# CH564L-R0-1v0.net
KiCad netlist of a schematic drawn in Altium Designer
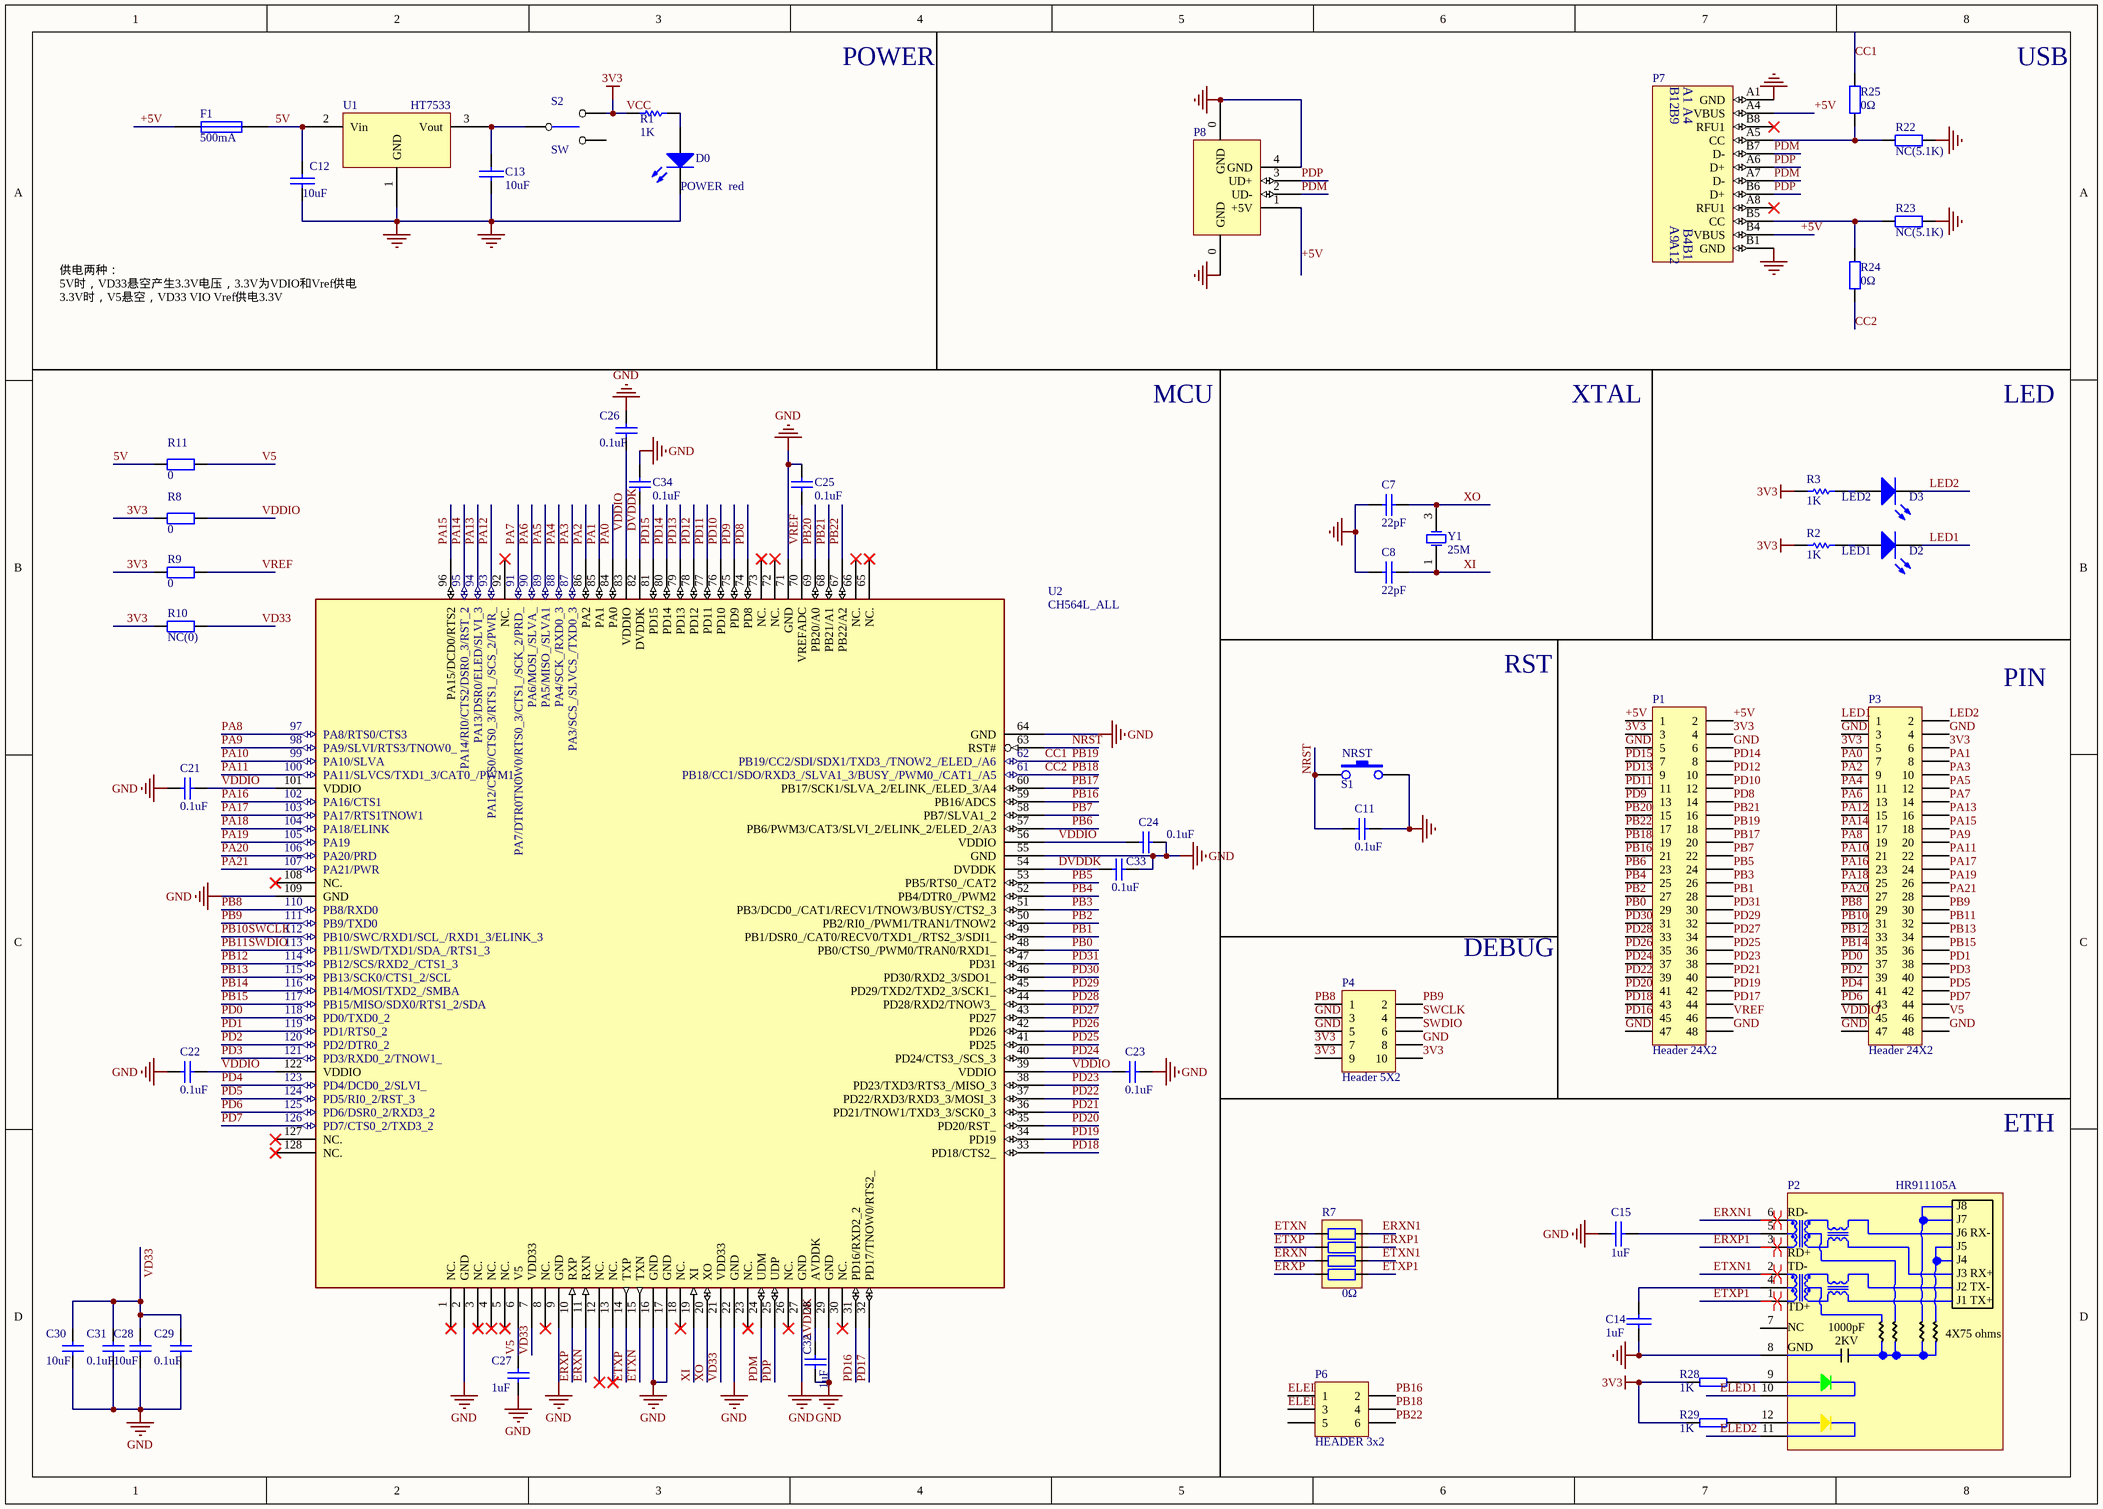
[diagram p0: CH564L-R0-1v0.SchDoc]

(export (version "E")
  (design (tool "Eeschema 10.0.6"))
  (components
    (comp (ref "C7")
      (value "22pF")
      (footprint "0402_C")
      (description "Capacitor")
      (fields (field (name "PUBLISHER") "Altium Limited"))
      (libsource (lib "*") (part "Cap"))
    )
    (comp (ref "C8")
      (value "22pF")
      (footprint "0402_C")
      (description "Capacitor")
      (fields (field (name "PUBLISHER") "Altium Limited"))
      (libsource (lib "*") (part "Cap"))
    )
    (comp (ref "C11")
      (value "0.1uF")
      (footprint "0402_C")
      (description "Capacitor")
      (fields (field (name "PUBLISHER") "Altium Limited"))
      (libsource (lib "*") (part "Cap"))
    )
    (comp (ref "C12")
      (value "10uF")
      (footprint "0603_C")
      (description "Capacitor")
      (libsource (lib "*") (part "CAP"))
    )
    (comp (ref "C13")
      (value "10uF")
      (footprint "0603_C")
      (description "Capacitor")
      (libsource (lib "*") (part "CAP"))
    )
    (comp (ref "C14")
      (value "1uF")
      (footprint "0402_C")
      (description "Capacitor")
      (libsource (lib "*") (part "CAP"))
    )
    (comp (ref "C15")
      (value "1uF")
      (footprint "0402_C")
      (description "Capacitor")
      (libsource (lib "*") (part "CAP"))
    )
    (comp (ref "C21")
      (value "0.1uF")
      (footprint "0402_C")
      (description "Capacitor")
      (fields (field (name "PUBLISHER") "Altium Limited"))
      (libsource (lib "MYLIB") (part "C-RAD-0603"))
    )
    (comp (ref "C22")
      (value "0.1uF")
      (footprint "0402_C")
      (description "Capacitor")
      (fields (field (name "PUBLISHER") "Altium Limited"))
      (libsource (lib "MYLIB") (part "C-RAD-0603"))
    )
    (comp (ref "C23")
      (value "0.1uF")
      (footprint "0402_C")
      (description "Capacitor")
      (fields (field (name "PUBLISHER") "Altium Limited"))
      (libsource (lib "MYLIB") (part "C-RAD-0603"))
    )
    (comp (ref "C24")
      (value "0.1uF")
      (footprint "0402_C")
      (description "Capacitor")
      (fields (field (name "PUBLISHER") "Altium Limited"))
      (libsource (lib "MYLIB") (part "C-RAD-0603"))
    )
    (comp (ref "C25")
      (value "0.1uF")
      (footprint "0402_C")
      (description "Capacitor")
      (fields (field (name "PUBLISHER") "Altium Limited"))
      (libsource (lib "MYLIB") (part "C-RAD-0603"))
    )
    (comp (ref "C26")
      (value "0.1uF")
      (footprint "0402_C")
      (description "Capacitor")
      (fields (field (name "PUBLISHER") "Altium Limited"))
      (libsource (lib "MYLIB") (part "C-RAD-0603"))
    )
    (comp (ref "C27")
      (value "1uF")
      (footprint "0402_C")
      (description "Capacitor")
      (fields (field (name "PUBLISHER") "Altium Limited"))
      (libsource (lib "MYLIB") (part "C-RAD-0603"))
    )
    (comp (ref "C28")
      (value "10uF")
      (footprint "0603_C")
      (description "Capacitor")
      (fields (field (name "PUBLISHER") "Altium Limited"))
      (libsource (lib "MYLIB") (part "C-RAD-0603"))
    )
    (comp (ref "C29")
      (value "0.1uF")
      (footprint "0402_C")
      (description "Capacitor")
      (fields (field (name "PUBLISHER") "Altium Limited"))
      (libsource (lib "MYLIB") (part "C-RAD-0603"))
    )
    (comp (ref "C30")
      (value "10uF")
      (footprint "0603_C")
      (description "Capacitor")
      (fields (field (name "PUBLISHER") "Altium Limited"))
      (libsource (lib "MYLIB") (part "C-RAD-0603"))
    )
    (comp (ref "C31")
      (value "0.1uF")
      (footprint "0402_C")
      (description "Capacitor")
      (fields (field (name "PUBLISHER") "Altium Limited"))
      (libsource (lib "MYLIB") (part "C-RAD-0603"))
    )
    (comp (ref "C32")
      (value "1uF")
      (footprint "0402_C")
      (description "Capacitor")
      (fields (field (name "PUBLISHER") "Altium Limited"))
      (libsource (lib "MYLIB") (part "C-RAD-0603"))
    )
    (comp (ref "C33")
      (value "0.1uF")
      (footprint "0402_C")
      (description "Capacitor")
      (fields (field (name "PUBLISHER") "Altium Limited"))
      (libsource (lib "MYLIB") (part "C-RAD-0603"))
    )
    (comp (ref "C34")
      (value "0.1uF")
      (footprint "0402_C")
      (description "Capacitor")
      (fields (field (name "PUBLISHER") "Altium Limited"))
      (libsource (lib "MYLIB") (part "C-RAD-0603"))
    )
    (comp (ref "D0")
      (value "POWER  red")
      (footprint "0603+")
      (description "Typical INFRARED GaAs LED")
      (fields (field (name "PUBLISHER") "Altium Limited"))
      (libsource (lib "*") (part "LED0"))
    )
    (comp (ref "D2")
      (value "LED1")
      (footprint "0603+")
      (description "Typical INFRARED GaAs LED")
      (fields (field (name "PUBLISHER") "Altium Limited"))
      (libsource (lib "*") (part "LED0"))
    )
    (comp (ref "D3")
      (value "LED2")
      (footprint "0603+")
      (description "Typical INFRARED GaAs LED")
      (fields (field (name "PUBLISHER") "Altium Limited"))
      (libsource (lib "*") (part "LED0"))
    )
    (comp (ref "F1")
      (value "500mA")
      (footprint "0603")
      (description "Fuse")
      (libsource (lib "*") (part "FUSE1"))
    )
    (comp (ref "P1")
      (value "Header 24X2")
      (footprint "IDC48-2.54mm")
      (description "Header, 24-Pin, Dual row")
      (fields (field (name "PUBLISHER") "Altium Limited"))
      (libsource (lib "Miscellaneous Connectors") (part "Header 24X2"))
    )
    (comp (ref "P2") (value "HR911105A") (footprint "HR911105A") (libsource (lib "*") (part "HR911105A")))
    (comp (ref "P3")
      (value "Header 24X2")
      (footprint "IDC48-2.54mm")
      (description "Header, 24-Pin, Dual row")
      (fields (field (name "PUBLISHER") "Altium Limited"))
      (libsource (lib "Miscellaneous Connectors") (part "Header 24X2"))
    )
    (comp (ref "P4")
      (value "Header 5X2")
      (footprint "IDC10-2.54mm")
      (description "Header, 5-Pin, Dual row")
      (fields (field (name "PUBLISHER") "Altium Limited"))
      (libsource (lib "Miscellaneous Connectors") (part "Header 5X2"))
    )
    (comp (ref "P6")
      (value "HEADER 3x2")
      (footprint "MYPCB:IDC6-2.54mm")
      (description "Header, 3-Pin, Dual row")
      (libsource (lib "wch_sch_others") (part "HEADER 3x2"))
    )
    (comp (ref "P7")
      (value "TYPE-C")
      (footprint "TYPE-C-Receptacle-2.0")
      (libsource (lib "*") (part "TYPE-C1"))
    )
    (comp (ref "P8")
      (value "USB_A")
      (footprint "USBAF")
      (description "USB Port")
      (libsource (lib "*") (part "USB"))
    )
    (comp (ref "R1")
      (value "1K")
      (footprint "0402")
      (description "Semiconductor Resistor")
      (libsource (lib "*") (part "Res Semi"))
    )
    (comp (ref "R2")
      (value "1K")
      (footprint "0402")
      (description "Semiconductor Resistor")
      (fields (field (name "PUBLISHER") "Altium Limited"))
      (libsource (lib "*") (part "Res Semi"))
    )
    (comp (ref "R3")
      (value "1K")
      (footprint "0402")
      (description "Semiconductor Resistor")
      (fields (field (name "PUBLISHER") "Altium Limited"))
      (libsource (lib "*") (part "Res Semi"))
    )
    (comp (ref "R7")
      (value "0Ω")
      (footprint "RCA-8P4R-0603")
      (description "贴片网络排阻")
      (fields (field (name "版权归属") "源创客"))
      (libsource (lib "wch_sch_others") (part "R-8P4R"))
    )
    (comp (ref "R8")
      (value "0")
      (footprint "0402")
      (description "Resistor")
      (fields (field (name "PUBLISHER") "Altium Limited"))
      (libsource (lib "*") (part "Res2"))
    )
    (comp (ref "R9")
      (value "0")
      (footprint "0402")
      (description "Resistor")
      (fields (field (name "PUBLISHER") "Altium Limited"))
      (libsource (lib "*") (part "Res2"))
    )
    (comp (ref "R10")
      (value "NC(0)")
      (footprint "0402")
      (description "Resistor")
      (fields (field (name "PUBLISHER") "Altium Limited"))
      (libsource (lib "*") (part "Res2"))
    )
    (comp (ref "R11")
      (value "0")
      (footprint "0402")
      (description "Resistor")
      (fields (field (name "PUBLISHER") "Altium Limited"))
      (libsource (lib "*") (part "Res2"))
    )
    (comp (ref "R22")
      (value "NC(5.1K)")
      (footprint "0402")
      (description "Resistor")
      (libsource (lib "Miscellaneous Devices") (part "Res2"))
    )
    (comp (ref "R23")
      (value "NC(5.1K)")
      (footprint "0402")
      (description "Resistor")
      (libsource (lib "Miscellaneous Devices") (part "Res2"))
    )
    (comp (ref "R24")
      (value "0Ω")
      (footprint "0402")
      (description "Resistor")
      (libsource (lib "") (part "Res2_1"))
    )
    (comp (ref "R25")
      (value "0Ω")
      (footprint "0402")
      (description "Resistor")
      (libsource (lib "") (part "Res2_1"))
    )
    (comp (ref "R28") (value "1K") (footprint "0402") (libsource (lib "wch_sch_others") (part "RES")))
    (comp (ref "R29") (value "1K") (footprint "0402") (libsource (lib "wch_sch_others") (part "RES")))
    (comp (ref "S1") (value "NRST") (footprint "SMD_6.1x3.65x2.5mm-KEY") (libsource (lib "*") (part "KEY")))
    (comp (ref "S2") (value "SW") (footprint "SW1") (libsource (lib "*") (part "SW")))
    (comp (ref "U1")
      (value "HT7533")
      (footprint "SOT-89")
      (libsource (lib "wch_sch_others") (part "1117-3.3V"))
    )
    (comp (ref "U2")
      (value "CH564L_ALL")
      (footprint "LQFP128")
      (description "RISC-V MCU with USB OTG 2.0 & 100Mbps Ethernet")
      (libsource (lib "DHXXXSCH") (part "CH564L_ALL"))
    )
    (comp (ref "Y1")
      (value "25M")
      (footprint "XT3225")
      (description "Crystal Oscillator")
      (fields (field (name "PUBLISHER") "Altium Limited"))
      (libsource (lib "*") (part "XTAL"))
    )
  )
  (nets
    (net (code "1") (name "/+5V") (class "Default")
      (node (ref "F1") (pin "1") (pinfunction "1_1") (pintype "passive"))
      (node (ref "P1") (pin "1") (pinfunction "1_1") (pintype "passive"))
      (node (ref "P1") (pin "2") (pinfunction "2_2") (pintype "passive"))
      (node (ref "P7") (pin "A4") (pinfunction "VBUS_A4") (pintype "bidirectional"))
      (node (ref "P7") (pin "B4") (pinfunction "VBUS_B4") (pintype "bidirectional"))
      (node (ref "P8") (pin "1") (pinfunction "+5V_1") (pintype "power_in"))
    )
    (net (code "2") (name "/5V") (class "Default")
      (node (ref "C12") (pin "1") (pinfunction "1_1") (pintype "passive"))
      (node (ref "F1") (pin "2") (pinfunction "2_2") (pintype "passive"))
      (node (ref "R11") (pin "2") (pinfunction "2_2") (pintype "passive"))
      (node (ref "U1") (pin "2") (pinfunction "Vin_2") (pintype "passive"))
    )
    (net (code "4") (name "/AVDDK") (class "Default")
      (node (ref "C32") (pin "2") (pinfunction "2_2") (pintype "passive"))
      (node (ref "U2") (pin "28") (pinfunction "AVDDK_28") (pintype "power_in"))
    )
    (net (code "5") (name "/CC1") (class "Default")
      (node (ref "P1") (pin "18") (pinfunction "18_18") (pintype "passive"))
      (node (ref "R25") (pin "2") (pinfunction "2_2") (pintype "passive"))
      (node (ref "U2") (pin "62") (pinfunction "PB19/CC2/SDI/SDX1/TXD3_/TNOW2_/ELED_/A6_62") (pintype "bidirectional"))
    )
    (net (code "6") (name "/CC2") (class "Default")
      (node (ref "P1") (pin "19") (pinfunction "19_19") (pintype "passive"))
      (node (ref "P6") (pin "4") (pinfunction "4_4") (pintype "passive"))
      (node (ref "R24") (pin "1") (pinfunction "1_1") (pintype "passive"))
      (node (ref "U2") (pin "61") (pinfunction "PB18/CC1/SDO/RXD3_/SLVA1_3/BUSY_/PWM0_/CAT1_/A5_61") (pintype "bidirectional"))
    )
    (net (code "7") (name "/DVDDK") (class "Default")
      (node (ref "C33") (pin "1") (pinfunction "1_1") (pintype "passive"))
      (node (ref "C34") (pin "1") (pinfunction "1_1") (pintype "passive"))
      (node (ref "U2") (pin "54") (pinfunction "DVDDK_54") (pintype "power_in"))
      (node (ref "U2") (pin "82") (pinfunction "DVDDK_82") (pintype "power_in"))
    )
    (net (code "8") (name "/ELED1") (class "Default")
      (node (ref "P2") (pin "10") (pintype "passive"))
      (node (ref "P6") (pin "3") (pinfunction "3_3") (pintype "passive"))
    )
    (net (code "9") (name "/ELED2") (class "Default")
      (node (ref "P2") (pin "11") (pintype "passive"))
      (node (ref "P6") (pin "1") (pinfunction "1_1") (pintype "passive"))
    )
    (net (code "10") (name "/ERXN") (class "Default")
      (node (ref "R7") (pin "3") (pinfunction "3_3") (pintype "passive"))
      (node (ref "U2") (pin "11") (pinfunction "RXN_11") (pintype "input"))
    )
    (net (code "11") (name "/ERXN1") (class "Default")
      (node (ref "P2") (pin "6") (pintype "passive"))
      (node (ref "R7") (pin "8") (pinfunction "8_8") (pintype "passive"))
    )
    (net (code "12") (name "/ERXP") (class "Default")
      (node (ref "R7") (pin "4") (pinfunction "4_4") (pintype "passive"))
      (node (ref "U2") (pin "10") (pinfunction "RXP_10") (pintype "input"))
    )
    (net (code "13") (name "/ERXP1") (class "Default")
      (node (ref "P2") (pin "3") (pintype "passive"))
      (node (ref "R7") (pin "7") (pinfunction "7_7") (pintype "passive"))
    )
    (net (code "14") (name "/ETXN") (class "Default")
      (node (ref "R7") (pin "1") (pinfunction "1_1") (pintype "passive"))
      (node (ref "U2") (pin "15") (pinfunction "TXN_15") (pintype "output"))
    )
    (net (code "15") (name "/ETXN1") (class "Default")
      (node (ref "P2") (pin "2") (pintype "passive"))
      (node (ref "R7") (pin "6") (pinfunction "6_6") (pintype "passive"))
    )
    (net (code "16") (name "/ETXP") (class "Default")
      (node (ref "R7") (pin "2") (pinfunction "2_2") (pintype "passive"))
      (node (ref "U2") (pin "14") (pinfunction "TXP_14") (pintype "output"))
    )
    (net (code "17") (name "/ETXP1") (class "Default")
      (node (ref "P2") (pin "1") (pintype "passive"))
      (node (ref "R7") (pin "5") (pinfunction "5_5") (pintype "passive"))
    )
    (net (code "18") (name "/LED1") (class "Default")
      (node (ref "D2") (pin "2") (pinfunction "K_2") (pintype "passive"))
      (node (ref "P3") (pin "1") (pinfunction "1_1") (pintype "passive"))
    )
    (net (code "19") (name "/LED2") (class "Default")
      (node (ref "D3") (pin "2") (pinfunction "K_2") (pintype "passive"))
      (node (ref "P3") (pin "2") (pinfunction "2_2") (pintype "passive"))
    )
    (net (code "20") (name "/NRST") (class "Default")
      (node (ref "C11") (pin "2") (pinfunction "2_2") (pintype "passive"))
      (node (ref "S1") (pin "1") (pinfunction "1_1") (pintype "passive"))
      (node (ref "U2") (pin "63") (pinfunction "RST#_63") (pintype "input"))
    )
    (net (code "21") (name "/PA0") (class "Default")
      (node (ref "P3") (pin "7") (pinfunction "7_7") (pintype "passive"))
      (node (ref "U2") (pin "84") (pinfunction "PA0_84") (pintype "bidirectional"))
    )
    (net (code "22") (name "/PA1") (class "Default")
      (node (ref "P3") (pin "8") (pinfunction "8_8") (pintype "passive"))
      (node (ref "U2") (pin "85") (pinfunction "PA1_85") (pintype "bidirectional"))
    )
    (net (code "23") (name "/PA2") (class "Default")
      (node (ref "P3") (pin "9") (pinfunction "9_9") (pintype "passive"))
      (node (ref "U2") (pin "86") (pinfunction "PA2_86") (pintype "bidirectional"))
    )
    (net (code "24") (name "/PA3") (class "Default")
      (node (ref "P3") (pin "10") (pinfunction "10_10") (pintype "passive"))
      (node (ref "U2") (pin "87") (pinfunction "PA3/SCS_/SLVCS_/TXD0_3_87") (pintype "bidirectional"))
    )
    (net (code "25") (name "/PA4") (class "Default")
      (node (ref "P3") (pin "11") (pinfunction "11_11") (pintype "passive"))
      (node (ref "U2") (pin "88") (pinfunction "PA4/SCK_/RXD0_3_88") (pintype "bidirectional"))
    )
    (net (code "26") (name "/PA5") (class "Default")
      (node (ref "P3") (pin "12") (pinfunction "12_12") (pintype "passive"))
      (node (ref "U2") (pin "89") (pinfunction "PA5/MISO_/SLVA1_89") (pintype "bidirectional"))
    )
    (net (code "27") (name "/PA6") (class "Default")
      (node (ref "P3") (pin "13") (pinfunction "13_13") (pintype "passive"))
      (node (ref "U2") (pin "90") (pinfunction "PA6/MOSI_/SLVA__90") (pintype "bidirectional"))
    )
    (net (code "28") (name "/PA7") (class "Default")
      (node (ref "P3") (pin "14") (pinfunction "14_14") (pintype "passive"))
      (node (ref "U2") (pin "91") (pinfunction "PA7/DTR0TNOW0/RTS0_3/CTS1_/SCK_2/PRD__91") (pintype "bidirectional"))
    )
    (net (code "29") (name "/PA8") (class "Default")
      (node (ref "P3") (pin "19") (pinfunction "19_19") (pintype "passive"))
      (node (ref "U2") (pin "97") (pinfunction "PA8/RTS0/CTS3_97") (pintype "bidirectional"))
    )
    (net (code "30") (name "/PA9") (class "Default")
      (node (ref "P3") (pin "20") (pinfunction "20_20") (pintype "passive"))
      (node (ref "U2") (pin "98") (pinfunction "PA9/SLVI/RTS3/TNOW0__98") (pintype "bidirectional"))
    )
    (net (code "31") (name "/PA10") (class "Default")
      (node (ref "P3") (pin "21") (pinfunction "21_21") (pintype "passive"))
      (node (ref "U2") (pin "99") (pinfunction "PA10/SLVA_99") (pintype "bidirectional"))
    )
    (net (code "32") (name "/PA11") (class "Default")
      (node (ref "P3") (pin "22") (pinfunction "22_22") (pintype "passive"))
      (node (ref "U2") (pin "100") (pinfunction "PA11/SLVCS/TXD1_3/CAT0_/PWM1__100") (pintype "bidirectional"))
    )
    (net (code "33") (name "/PA12") (class "Default")
      (node (ref "P3") (pin "15") (pinfunction "15_15") (pintype "passive"))
      (node (ref "U2") (pin "93") (pinfunction "PA12/CTS0/CTS0_3/RTS1_/SCS_2/PWR__93") (pintype "bidirectional"))
    )
    (net (code "34") (name "/PA13") (class "Default")
      (node (ref "P3") (pin "16") (pinfunction "16_16") (pintype "passive"))
      (node (ref "U2") (pin "94") (pinfunction "PA13/DSR0/ELED/SLVI_3_94") (pintype "bidirectional"))
    )
    (net (code "35") (name "/PA14") (class "Default")
      (node (ref "P3") (pin "17") (pinfunction "17_17") (pintype "passive"))
      (node (ref "U2") (pin "95") (pinfunction "PA14/RI0/CTS2/DSR0_3/RST_2_95") (pintype "bidirectional"))
    )
    (net (code "36") (name "/PA15") (class "Default")
      (node (ref "P3") (pin "18") (pinfunction "18_18") (pintype "passive"))
      (node (ref "U2") (pin "96") (pinfunction "PA15/DCD0/RTS2_96") (pintype "bidirectional"))
    )
    (net (code "37") (name "/PA16") (class "Default")
      (node (ref "P3") (pin "23") (pinfunction "23_23") (pintype "passive"))
      (node (ref "U2") (pin "102") (pinfunction "PA16/CTS1_102") (pintype "bidirectional"))
    )
    (net (code "38") (name "/PA17") (class "Default")
      (node (ref "P3") (pin "24") (pinfunction "24_24") (pintype "passive"))
      (node (ref "U2") (pin "103") (pinfunction "PA17/RTS1TNOW1_103") (pintype "bidirectional"))
    )
    (net (code "39") (name "/PA18") (class "Default")
      (node (ref "P3") (pin "25") (pinfunction "25_25") (pintype "passive"))
      (node (ref "U2") (pin "104") (pinfunction "PA18/ELINK_104") (pintype "bidirectional"))
    )
    (net (code "40") (name "/PA19") (class "Default")
      (node (ref "P3") (pin "26") (pinfunction "26_26") (pintype "passive"))
      (node (ref "U2") (pin "105") (pinfunction "PA19_105") (pintype "bidirectional"))
    )
    (net (code "41") (name "/PA20") (class "Default")
      (node (ref "P3") (pin "27") (pinfunction "27_27") (pintype "passive"))
      (node (ref "U2") (pin "106") (pinfunction "PA20/PRD_106") (pintype "bidirectional"))
    )
    (net (code "42") (name "/PA21") (class "Default")
      (node (ref "P3") (pin "28") (pinfunction "28_28") (pintype "passive"))
      (node (ref "U2") (pin "107") (pinfunction "PA21/PWR_107") (pintype "bidirectional"))
    )
    (net (code "43") (name "/PB0") (class "Default")
      (node (ref "P1") (pin "29") (pinfunction "29_29") (pintype "passive"))
      (node (ref "U2") (pin "48") (pinfunction "PB0/CTS0_/PWM0/TRAN0/RXD1__48") (pintype "bidirectional"))
    )
    (net (code "44") (name "/PB1") (class "Default")
      (node (ref "P1") (pin "28") (pinfunction "28_28") (pintype "passive"))
      (node (ref "U2") (pin "49") (pinfunction "PB1/DSR0_/CAT0/RECV0/TXD1_/RTS2_3/SDI1__49") (pintype "bidirectional"))
    )
    (net (code "45") (name "/PB2") (class "Default")
      (node (ref "P1") (pin "27") (pinfunction "27_27") (pintype "passive"))
      (node (ref "U2") (pin "50") (pinfunction "PB2/RI0_/PWM1/TRAN1/TNOW2_50") (pintype "bidirectional"))
    )
    (net (code "46") (name "/PB3") (class "Default")
      (node (ref "P1") (pin "26") (pinfunction "26_26") (pintype "passive"))
      (node (ref "U2") (pin "51") (pinfunction "PB3/DCD0_/CAT1/RECV1/TNOW3/BUSY/CTS2_3_51") (pintype "bidirectional"))
    )
    (net (code "47") (name "/PB4") (class "Default")
      (node (ref "P1") (pin "25") (pinfunction "25_25") (pintype "passive"))
      (node (ref "U2") (pin "52") (pinfunction "PB4/DTR0_/PWM2_52") (pintype "bidirectional"))
    )
    (net (code "48") (name "/PB5") (class "Default")
      (node (ref "P1") (pin "24") (pinfunction "24_24") (pintype "passive"))
      (node (ref "U2") (pin "53") (pinfunction "PB5/RTS0_/CAT2_53") (pintype "bidirectional"))
    )
    (net (code "49") (name "/PB6") (class "Default")
      (node (ref "P1") (pin "23") (pinfunction "23_23") (pintype "passive"))
      (node (ref "U2") (pin "57") (pinfunction "PB6/PWM3/CAT3/SLVI_2/ELINK_2/ELED_2/A3_57") (pintype "bidirectional"))
    )
    (net (code "50") (name "/PB7") (class "Default")
      (node (ref "P1") (pin "22") (pinfunction "22_22") (pintype "passive"))
      (node (ref "U2") (pin "58") (pinfunction "PB7/SLVA1_2_58") (pintype "bidirectional"))
    )
    (net (code "51") (name "/PB8") (class "Default")
      (node (ref "P3") (pin "29") (pinfunction "29_29") (pintype "passive"))
      (node (ref "P4") (pin "1") (pinfunction "1_1") (pintype "passive"))
      (node (ref "U2") (pin "110") (pinfunction "PB8/RXD0_110") (pintype "bidirectional"))
    )
    (net (code "52") (name "/PB9") (class "Default")
      (node (ref "P3") (pin "30") (pinfunction "30_30") (pintype "passive"))
      (node (ref "P4") (pin "2") (pinfunction "2_2") (pintype "passive"))
      (node (ref "U2") (pin "111") (pinfunction "PB9/TXD0_111") (pintype "bidirectional"))
    )
    (net (code "53") (name "/PB10") (class "Default")
      (node (ref "P3") (pin "31") (pinfunction "31_31") (pintype "passive"))
      (node (ref "P4") (pin "4") (pinfunction "4_4") (pintype "passive"))
      (node (ref "U2") (pin "112") (pinfunction "PB10/SWC/RXD1/SCL_/RXD1_3/ELINK_3_112") (pintype "bidirectional"))
    )
    (net (code "54") (name "/PB11") (class "Default")
      (node (ref "P3") (pin "32") (pinfunction "32_32") (pintype "passive"))
      (node (ref "P4") (pin "6") (pinfunction "6_6") (pintype "passive"))
      (node (ref "U2") (pin "113") (pinfunction "PB11/SWD/TXD1/SDA_/RTS1_3_113") (pintype "bidirectional"))
    )
    (net (code "55") (name "/PB12") (class "Default")
      (node (ref "P3") (pin "33") (pinfunction "33_33") (pintype "passive"))
      (node (ref "U2") (pin "114") (pinfunction "PB12/SCS/RXD2_/CTS1_3_114") (pintype "bidirectional"))
    )
    (net (code "56") (name "/PB13") (class "Default")
      (node (ref "P3") (pin "34") (pinfunction "34_34") (pintype "passive"))
      (node (ref "U2") (pin "115") (pinfunction "PB13/SCK0/CTS1_2/SCL_115") (pintype "bidirectional"))
    )
    (net (code "57") (name "/PB14") (class "Default")
      (node (ref "P3") (pin "35") (pinfunction "35_35") (pintype "passive"))
      (node (ref "U2") (pin "116") (pinfunction "PB14/MOSI/TXD2_/SMBA_116") (pintype "bidirectional"))
    )
    (net (code "58") (name "/PB15") (class "Default")
      (node (ref "P3") (pin "36") (pinfunction "36_36") (pintype "passive"))
      (node (ref "U2") (pin "117") (pinfunction "PB15/MISO/SDX0/RTS1_2/SDA_117") (pintype "bidirectional"))
    )
    (net (code "59") (name "/PB16") (class "Default")
      (node (ref "P1") (pin "21") (pinfunction "21_21") (pintype "passive"))
      (node (ref "P6") (pin "2") (pinfunction "2_2") (pintype "passive"))
      (node (ref "U2") (pin "59") (pinfunction "PB16/ADCS_59") (pintype "bidirectional"))
    )
    (net (code "60") (name "/PB17") (class "Default")
      (node (ref "P1") (pin "20") (pinfunction "20_20") (pintype "passive"))
      (node (ref "U2") (pin "60") (pinfunction "PB17/SCK1/SLVA_2/ELINK_/ELED_3/A4_60") (pintype "bidirectional"))
    )
    (net (code "61") (name "/PB20") (class "Default")
      (node (ref "P1") (pin "15") (pinfunction "15_15") (pintype "passive"))
      (node (ref "U2") (pin "69") (pinfunction "PB20/A0_69") (pintype "bidirectional"))
    )
    (net (code "62") (name "/PB21") (class "Default")
      (node (ref "P1") (pin "16") (pinfunction "16_16") (pintype "passive"))
      (node (ref "U2") (pin "68") (pinfunction "PB21/A1_68") (pintype "bidirectional"))
    )
    (net (code "63") (name "/PB22") (class "Default")
      (node (ref "P1") (pin "17") (pinfunction "17_17") (pintype "passive"))
      (node (ref "P6") (pin "6") (pinfunction "6_6") (pintype "passive"))
      (node (ref "U2") (pin "67") (pinfunction "PB22/A2_67") (pintype "bidirectional"))
    )
    (net (code "64") (name "/PD0") (class "Default")
      (node (ref "P3") (pin "37") (pinfunction "37_37") (pintype "passive"))
      (node (ref "U2") (pin "118") (pinfunction "PD0/TXD0_2_118") (pintype "bidirectional"))
    )
    (net (code "65") (name "/PD1") (class "Default")
      (node (ref "P3") (pin "38") (pinfunction "38_38") (pintype "passive"))
      (node (ref "U2") (pin "119") (pinfunction "PD1/RTS0_2_119") (pintype "bidirectional"))
    )
    (net (code "66") (name "/PD2") (class "Default")
      (node (ref "P3") (pin "39") (pinfunction "39_39") (pintype "passive"))
      (node (ref "U2") (pin "120") (pinfunction "PD2/DTR0_2_120") (pintype "bidirectional"))
    )
    (net (code "67") (name "/PD3") (class "Default")
      (node (ref "P3") (pin "40") (pinfunction "40_40") (pintype "passive"))
      (node (ref "U2") (pin "121") (pinfunction "PD3/RXD0_2/TNOW1__121") (pintype "bidirectional"))
    )
    (net (code "68") (name "/PD4") (class "Default")
      (node (ref "P3") (pin "41") (pinfunction "41_41") (pintype "passive"))
      (node (ref "U2") (pin "123") (pinfunction "PD4/DCD0_2/SLVI__123") (pintype "bidirectional"))
    )
    (net (code "69") (name "/PD5") (class "Default")
      (node (ref "P3") (pin "42") (pinfunction "42_42") (pintype "passive"))
      (node (ref "U2") (pin "124") (pinfunction "PD5/RI0_2/RST_3_124") (pintype "bidirectional"))
    )
    (net (code "70") (name "/PD6") (class "Default")
      (node (ref "P3") (pin "43") (pinfunction "43_43") (pintype "passive"))
      (node (ref "U2") (pin "125") (pinfunction "PD6/DSR0_2/RXD3_2_125") (pintype "bidirectional"))
    )
    (net (code "71") (name "/PD7") (class "Default")
      (node (ref "P3") (pin "44") (pinfunction "44_44") (pintype "passive"))
      (node (ref "U2") (pin "126") (pinfunction "PD7/CTS0_2/TXD3_2_126") (pintype "bidirectional"))
    )
    (net (code "72") (name "/PD8") (class "Default")
      (node (ref "P1") (pin "14") (pinfunction "14_14") (pintype "passive"))
      (node (ref "U2") (pin "74") (pinfunction "PD8_74") (pintype "bidirectional"))
    )
    (net (code "73") (name "/PD9") (class "Default")
      (node (ref "P1") (pin "13") (pinfunction "13_13") (pintype "passive"))
      (node (ref "U2") (pin "75") (pinfunction "PD9_75") (pintype "bidirectional"))
    )
    (net (code "74") (name "/PD10") (class "Default")
      (node (ref "P1") (pin "12") (pinfunction "12_12") (pintype "passive"))
      (node (ref "U2") (pin "76") (pinfunction "PD10_76") (pintype "bidirectional"))
    )
    (net (code "75") (name "/PD11") (class "Default")
      (node (ref "P1") (pin "11") (pinfunction "11_11") (pintype "passive"))
      (node (ref "U2") (pin "77") (pinfunction "PD11_77") (pintype "bidirectional"))
    )
    (net (code "76") (name "/PD12") (class "Default")
      (node (ref "P1") (pin "10") (pinfunction "10_10") (pintype "passive"))
      (node (ref "U2") (pin "78") (pinfunction "PD12_78") (pintype "bidirectional"))
    )
    (net (code "77") (name "/PD13") (class "Default")
      (node (ref "P1") (pin "9") (pinfunction "9_9") (pintype "passive"))
      (node (ref "U2") (pin "79") (pinfunction "PD13_79") (pintype "bidirectional"))
    )
    (net (code "78") (name "/PD14") (class "Default")
      (node (ref "P1") (pin "8") (pinfunction "8_8") (pintype "passive"))
      (node (ref "U2") (pin "80") (pinfunction "PD14_80") (pintype "bidirectional"))
    )
    (net (code "79") (name "/PD15") (class "Default")
      (node (ref "P1") (pin "7") (pinfunction "7_7") (pintype "passive"))
      (node (ref "U2") (pin "81") (pinfunction "PD15_81") (pintype "bidirectional"))
    )
    (net (code "80") (name "/PD16") (class "Default")
      (node (ref "P1") (pin "45") (pinfunction "45_45") (pintype "passive"))
      (node (ref "U2") (pin "31") (pinfunction "PD16/RXD2_2_31") (pintype "bidirectional"))
    )
    (net (code "81") (name "/PD17") (class "Default")
      (node (ref "P1") (pin "44") (pinfunction "44_44") (pintype "passive"))
      (node (ref "U2") (pin "32") (pinfunction "PD17/TNOW0/RTS2__32") (pintype "bidirectional"))
    )
    (net (code "82") (name "/PD18") (class "Default")
      (node (ref "P1") (pin "43") (pinfunction "43_43") (pintype "passive"))
      (node (ref "U2") (pin "33") (pinfunction "PD18/CTS2__33") (pintype "bidirectional"))
    )
    (net (code "83") (name "/PD19") (class "Default")
      (node (ref "P1") (pin "42") (pinfunction "42_42") (pintype "passive"))
      (node (ref "U2") (pin "34") (pinfunction "PD19_34") (pintype "bidirectional"))
    )
    (net (code "84") (name "/PD20") (class "Default")
      (node (ref "P1") (pin "41") (pinfunction "41_41") (pintype "passive"))
      (node (ref "U2") (pin "35") (pinfunction "PD20/RST__35") (pintype "bidirectional"))
    )
    (net (code "85") (name "/PD21") (class "Default")
      (node (ref "P1") (pin "40") (pinfunction "40_40") (pintype "passive"))
      (node (ref "U2") (pin "36") (pinfunction "PD21/TNOW1/TXD3_3/SCK0_3_36") (pintype "bidirectional"))
    )
    (net (code "86") (name "/PD22") (class "Default")
      (node (ref "P1") (pin "39") (pinfunction "39_39") (pintype "passive"))
      (node (ref "U2") (pin "37") (pinfunction "PD22/RXD3/RXD3_3/MOSI_3_37") (pintype "bidirectional"))
    )
    (net (code "87") (name "/PD23") (class "Default")
      (node (ref "P1") (pin "38") (pinfunction "38_38") (pintype "passive"))
      (node (ref "U2") (pin "38") (pinfunction "PD23/TXD3/RTS3_/MISO_3_38") (pintype "bidirectional"))
    )
    (net (code "88") (name "/PD24") (class "Default")
      (node (ref "P1") (pin "37") (pinfunction "37_37") (pintype "passive"))
      (node (ref "U2") (pin "40") (pinfunction "PD24/CTS3_/SCS_3_40") (pintype "bidirectional"))
    )
    (net (code "89") (name "/PD25") (class "Default")
      (node (ref "P1") (pin "36") (pinfunction "36_36") (pintype "passive"))
      (node (ref "U2") (pin "41") (pinfunction "PD25_41") (pintype "bidirectional"))
    )
    (net (code "90") (name "/PD26") (class "Default")
      (node (ref "P1") (pin "35") (pinfunction "35_35") (pintype "passive"))
      (node (ref "U2") (pin "42") (pinfunction "PD26_42") (pintype "bidirectional"))
    )
    (net (code "91") (name "/PD27") (class "Default")
      (node (ref "P1") (pin "34") (pinfunction "34_34") (pintype "passive"))
      (node (ref "U2") (pin "43") (pinfunction "PD27_43") (pintype "bidirectional"))
    )
    (net (code "92") (name "/PD28") (class "Default")
      (node (ref "P1") (pin "33") (pinfunction "33_33") (pintype "passive"))
      (node (ref "U2") (pin "44") (pinfunction "PD28/RXD2/TNOW3__44") (pintype "bidirectional"))
    )
    (net (code "93") (name "/PD29") (class "Default")
      (node (ref "P1") (pin "32") (pinfunction "32_32") (pintype "passive"))
      (node (ref "U2") (pin "45") (pinfunction "PD29/TXD2/TXD2_3/SCK1__45") (pintype "bidirectional"))
    )
    (net (code "94") (name "/PD30") (class "Default")
      (node (ref "P1") (pin "31") (pinfunction "31_31") (pintype "passive"))
      (node (ref "U2") (pin "46") (pinfunction "PD30/RXD2_3/SDO1__46") (pintype "bidirectional"))
    )
    (net (code "95") (name "/PD31") (class "Default")
      (node (ref "P1") (pin "30") (pinfunction "30_30") (pintype "passive"))
      (node (ref "U2") (pin "47") (pinfunction "PD31_47") (pintype "bidirectional"))
    )
    (net (code "96") (name "/PDM") (class "Default")
      (node (ref "P7") (pin "A7") (pinfunction "D-_A7") (pintype "bidirectional"))
      (node (ref "P7") (pin "B7") (pinfunction "D-_B7") (pintype "bidirectional"))
      (node (ref "P8") (pin "2") (pinfunction "UD-_2") (pintype "bidirectional"))
      (node (ref "U2") (pin "24") (pinfunction "UDM_24") (pintype "bidirectional"))
    )
    (net (code "97") (name "/PDP") (class "Default")
      (node (ref "P7") (pin "A6") (pinfunction "D+_A6") (pintype "bidirectional"))
      (node (ref "P7") (pin "B6") (pinfunction "D+_B6") (pintype "bidirectional"))
      (node (ref "P8") (pin "3") (pinfunction "UD+_3") (pintype "bidirectional"))
      (node (ref "U2") (pin "25") (pinfunction "UDP_25") (pintype "bidirectional"))
    )
    (net (code "98") (name "/V5") (class "Default")
      (node (ref "C27") (pin "2") (pinfunction "2_2") (pintype "passive"))
      (node (ref "P3") (pin "46") (pinfunction "46_46") (pintype "passive"))
      (node (ref "R11") (pin "1") (pinfunction "1_1") (pintype "passive"))
      (node (ref "U2") (pin "6") (pinfunction "V5_6") (pintype "power_in"))
    )
    (net (code "99") (name "/VD33") (class "Default")
      (node (ref "C28") (pin "2") (pinfunction "2_2") (pintype "passive"))
      (node (ref "C29") (pin "2") (pinfunction "2_2") (pintype "passive"))
      (node (ref "C30") (pin "2") (pinfunction "2_2") (pintype "passive"))
      (node (ref "C31") (pin "2") (pinfunction "2_2") (pintype "passive"))
      (node (ref "R10") (pin "1") (pinfunction "1_1") (pintype "passive"))
      (node (ref "U2") (pin "21") (pinfunction "VDD33_21") (pintype "power_in"))
      (node (ref "U2") (pin "7") (pinfunction "VDD33_7") (pintype "power_in"))
    )
    (net (code "100") (name "/VDDIO") (class "Default")
      (node (ref "C21") (pin "2") (pinfunction "2_2") (pintype "passive"))
      (node (ref "C22") (pin "2") (pinfunction "2_2") (pintype "passive"))
      (node (ref "C23") (pin "1") (pinfunction "1_1") (pintype "passive"))
      (node (ref "C24") (pin "1") (pinfunction "1_1") (pintype "passive"))
      (node (ref "C26") (pin "1") (pinfunction "1_1") (pintype "passive"))
      (node (ref "P3") (pin "45") (pinfunction "45_45") (pintype "passive"))
      (node (ref "R8") (pin "1") (pinfunction "1_1") (pintype "passive"))
      (node (ref "U2") (pin "101") (pinfunction "VDDIO_101") (pintype "power_in"))
      (node (ref "U2") (pin "122") (pinfunction "VDDIO_122") (pintype "power_in"))
      (node (ref "U2") (pin "39") (pinfunction "VDDIO_39") (pintype "power_in"))
      (node (ref "U2") (pin "56") (pinfunction "VDDIO_56") (pintype "power_in"))
      (node (ref "U2") (pin "83") (pinfunction "VDDIO_83") (pintype "power_in"))
    )
    (net (code "101") (name "/VREF") (class "Default")
      (node (ref "C25") (pin "1") (pinfunction "1_1") (pintype "passive"))
      (node (ref "P1") (pin "46") (pinfunction "46_46") (pintype "passive"))
      (node (ref "R9") (pin "1") (pinfunction "1_1") (pintype "passive"))
      (node (ref "U2") (pin "70") (pinfunction "VREFADC_70") (pintype "power_in"))
    )
    (net (code "102") (name "/XI") (class "Default")
      (node (ref "C8") (pin "2") (pinfunction "2_2") (pintype "passive"))
      (node (ref "U2") (pin "19") (pinfunction "XI_19") (pintype "input"))
      (node (ref "Y1") (pin "1") (pinfunction "OSC1_1") (pintype "passive"))
    )
    (net (code "103") (name "/XO") (class "Default")
      (node (ref "C7") (pin "2") (pinfunction "2_2") (pintype "passive"))
      (node (ref "U2") (pin "20") (pinfunction "XO_20") (pintype "bidirectional"))
      (node (ref "Y1") (pin "3") (pinfunction "OSC2_3") (pintype "passive"))
    )
    (net (code "104") (name "3V3") (class "Default")
      (node (ref "P1") (pin "3") (pinfunction "3_3") (pintype "passive"))
      (node (ref "P1") (pin "4") (pinfunction "4_4") (pintype "passive"))
      (node (ref "P3") (pin "5") (pinfunction "5_5") (pintype "passive"))
      (node (ref "P3") (pin "6") (pinfunction "6_6") (pintype "passive"))
      (node (ref "P4") (pin "10") (pinfunction "10_10") (pintype "passive"))
      (node (ref "P4") (pin "7") (pinfunction "7_7") (pintype "passive"))
      (node (ref "P4") (pin "9") (pinfunction "9_9") (pintype "passive"))
      (node (ref "R1") (pin "2") (pinfunction "2_2") (pintype "passive"))
      (node (ref "R10") (pin "2") (pinfunction "2_2") (pintype "passive"))
      (node (ref "R2") (pin "1") (pinfunction "1_1") (pintype "passive"))
      (node (ref "R28") (pin "1") (pintype "passive"))
      (node (ref "R29") (pin "1") (pintype "passive"))
      (node (ref "R3") (pin "1") (pinfunction "1_1") (pintype "passive"))
      (node (ref "R8") (pin "2") (pinfunction "2_2") (pintype "passive"))
      (node (ref "R9") (pin "2") (pinfunction "2_2") (pintype "passive"))
      (node (ref "S2") (pin "3") (pinfunction "3_3") (pintype "passive"))
    )
    (net (code "105") (name "GND") (class "Default")
      (node (ref "C11") (pin "1") (pinfunction "1_1") (pintype "passive"))
      (node (ref "C12") (pin "2") (pinfunction "2_2") (pintype "passive"))
      (node (ref "C13") (pin "2") (pinfunction "2_2") (pintype "passive"))
      (node (ref "C14") (pin "1") (pinfunction "1_1") (pintype "passive"))
      (node (ref "C15") (pin "2") (pinfunction "2_2") (pintype "passive"))
      (node (ref "C21") (pin "1") (pinfunction "1_1") (pintype "passive"))
      (node (ref "C22") (pin "1") (pinfunction "1_1") (pintype "passive"))
      (node (ref "C23") (pin "2") (pinfunction "2_2") (pintype "passive"))
      (node (ref "C24") (pin "2") (pinfunction "2_2") (pintype "passive"))
      (node (ref "C25") (pin "2") (pinfunction "2_2") (pintype "passive"))
      (node (ref "C26") (pin "2") (pinfunction "2_2") (pintype "passive"))
      (node (ref "C27") (pin "1") (pinfunction "1_1") (pintype "passive"))
      (node (ref "C28") (pin "1") (pinfunction "1_1") (pintype "passive"))
      (node (ref "C29") (pin "1") (pinfunction "1_1") (pintype "passive"))
      (node (ref "C30") (pin "1") (pinfunction "1_1") (pintype "passive"))
      (node (ref "C31") (pin "1") (pinfunction "1_1") (pintype "passive"))
      (node (ref "C32") (pin "1") (pinfunction "1_1") (pintype "passive"))
      (node (ref "C33") (pin "2") (pinfunction "2_2") (pintype "passive"))
      (node (ref "C34") (pin "2") (pinfunction "2_2") (pintype "passive"))
      (node (ref "C7") (pin "1") (pinfunction "1_1") (pintype "passive"))
      (node (ref "C8") (pin "1") (pinfunction "1_1") (pintype "passive"))
      (node (ref "D0") (pin "2") (pinfunction "K_2") (pintype "passive"))
      (node (ref "P1") (pin "47") (pinfunction "47_47") (pintype "passive"))
      (node (ref "P1") (pin "48") (pinfunction "48_48") (pintype "passive"))
      (node (ref "P1") (pin "5") (pinfunction "5_5") (pintype "passive"))
      (node (ref "P1") (pin "6") (pinfunction "6_6") (pintype "passive"))
      (node (ref "P2") (pin "8") (pintype "passive"))
      (node (ref "P3") (pin "3") (pinfunction "3_3") (pintype "passive"))
      (node (ref "P3") (pin "4") (pinfunction "4_4") (pintype "passive"))
      (node (ref "P3") (pin "47") (pinfunction "47_47") (pintype "passive"))
      (node (ref "P3") (pin "48") (pinfunction "48_48") (pintype "passive"))
      (node (ref "P4") (pin "3") (pinfunction "3_3") (pintype "passive"))
      (node (ref "P4") (pin "5") (pinfunction "5_5") (pintype "passive"))
      (node (ref "P4") (pin "8") (pinfunction "8_8") (pintype "passive"))
      (node (ref "P7") (pin "A1") (pinfunction "GND_A1") (pintype "bidirectional"))
      (node (ref "P7") (pin "B1") (pinfunction "GND_B1") (pintype "bidirectional"))
      (node (ref "P8") (pin "0") (pinfunction "GND_0") (pintype "power_in"))
      (node (ref "P8") (pin "4") (pinfunction "GND_4") (pintype "power_in"))
      (node (ref "R22") (pin "2") (pinfunction "2_2") (pintype "passive"))
      (node (ref "R23") (pin "2") (pinfunction "2_2") (pintype "passive"))
      (node (ref "S1") (pin "2") (pinfunction "2_2") (pintype "passive"))
      (node (ref "U1") (pin "1") (pinfunction "GND_1") (pintype "passive"))
      (node (ref "U2") (pin "109") (pinfunction "GND_109") (pintype "power_in"))
      (node (ref "U2") (pin "16") (pinfunction "GND_16") (pintype "power_in"))
      (node (ref "U2") (pin "17") (pinfunction "GND_17") (pintype "power_in"))
      (node (ref "U2") (pin "2") (pinfunction "GND_2") (pintype "power_in"))
      (node (ref "U2") (pin "22") (pinfunction "GND_22") (pintype "power_in"))
      (node (ref "U2") (pin "27") (pinfunction "GND_27") (pintype "power_in"))
      (node (ref "U2") (pin "29") (pinfunction "GND_29") (pintype "power_in"))
      (node (ref "U2") (pin "55") (pinfunction "GND_55") (pintype "power_in"))
      (node (ref "U2") (pin "64") (pinfunction "GND_64") (pintype "power_in"))
      (node (ref "U2") (pin "71") (pinfunction "GND_71") (pintype "power_in"))
      (node (ref "U2") (pin "9") (pinfunction "GND_9") (pintype "power_in"))
    )
    (net (code "106") (name "Net-(C14-Pad2)") (class "Default")
      (node (ref "C14") (pin "2") (pinfunction "2_2") (pintype "passive"))
      (node (ref "P2") (pin "4") (pintype "passive"))
    )
    (net (code "107") (name "Net-(C15-Pad1)") (class "Default")
      (node (ref "C15") (pin "1") (pinfunction "1_1") (pintype "passive"))
      (node (ref "P2") (pin "5") (pintype "passive"))
    )
    (net (code "108") (name "Net-(D0-A)") (class "Default")
      (node (ref "D0") (pin "1") (pinfunction "A_1") (pintype "passive"))
      (node (ref "R1") (pin "1") (pinfunction "1_1") (pintype "passive"))
    )
    (net (code "109") (name "Net-(D2-A)") (class "Default")
      (node (ref "D2") (pin "1") (pinfunction "A_1") (pintype "passive"))
      (node (ref "R2") (pin "2") (pinfunction "2_2") (pintype "passive"))
    )
    (net (code "110") (name "Net-(D3-A)") (class "Default")
      (node (ref "D3") (pin "1") (pinfunction "A_1") (pintype "passive"))
      (node (ref "R3") (pin "2") (pinfunction "2_2") (pintype "passive"))
    )
    (net (code "111") (name "Net-(P2-Pad9)") (class "Default")
      (node (ref "P2") (pin "9") (pintype "passive"))
      (node (ref "R28") (pin "2") (pintype "passive"))
    )
    (net (code "112") (name "Net-(P2-Pad12)") (class "Default")
      (node (ref "P2") (pin "12") (pintype "passive"))
      (node (ref "R29") (pin "2") (pintype "passive"))
    )
    (net (code "113") (name "Net-(P7-CC-PadA5)") (class "Default")
      (node (ref "P7") (pin "A5") (pinfunction "CC_A5") (pintype "bidirectional"))
      (node (ref "R22") (pin "1") (pinfunction "1_1") (pintype "passive"))
      (node (ref "R25") (pin "1") (pinfunction "1_1") (pintype "passive"))
    )
    (net (code "114") (name "Net-(P7-CC-PadB5)") (class "Default")
      (node (ref "P7") (pin "B5") (pinfunction "CC_B5") (pintype "bidirectional"))
      (node (ref "R23") (pin "1") (pinfunction "1_1") (pintype "passive"))
      (node (ref "R24") (pin "2") (pinfunction "2_2") (pintype "passive"))
    )
    (net (code "115") (name "Net-(U1-Vout)") (class "Default")
      (node (ref "C13") (pin "1") (pinfunction "1_1") (pintype "passive"))
      (node (ref "S2") (pin "1") (pinfunction "1_1") (pintype "passive"))
      (node (ref "U1") (pin "3") (pinfunction "Vout_3") (pintype "passive"))
    )
    (net (code "116") (name "unconnected-(P2-Pad7)") (class "Default")
      (node (ref "P2") (pin "7") (pintype "passive"))
    )
    (net (code "117") (name "unconnected-(P6-Pad5)") (class "Default")
      (node (ref "P6") (pin "5") (pinfunction "5_5") (pintype "passive"))
    )
    (net (code "118") (name "unconnected-(P7-RFU1-PadA8)") (class "Default")
      (node (ref "P7") (pin "A8") (pinfunction "RFU1_A8") (pintype "bidirectional+no_connect"))
    )
    (net (code "119") (name "unconnected-(P7-RFU1-PadB8)") (class "Default")
      (node (ref "P7") (pin "B8") (pinfunction "RFU1_B8") (pintype "bidirectional+no_connect"))
    )
    (net (code "120") (name "unconnected-(S2-Pad2)") (class "Default")
      (node (ref "S2") (pin "2") (pinfunction "2_2") (pintype "passive"))
    )
    (net (code "121") (name "unconnected-(U2-NC.-Pad1)") (class "Default")
      (node (ref "U2") (pin "1") (pinfunction "NC._1") (pintype "passive+no_connect"))
    )
    (net (code "122") (name "unconnected-(U2-NC.-Pad3)") (class "Default")
      (node (ref "U2") (pin "3") (pinfunction "NC._3") (pintype "passive+no_connect"))
    )
    (net (code "123") (name "unconnected-(U2-NC.-Pad4)") (class "Default")
      (node (ref "U2") (pin "4") (pinfunction "NC._4") (pintype "passive+no_connect"))
    )
    (net (code "124") (name "unconnected-(U2-NC.-Pad5)") (class "Default")
      (node (ref "U2") (pin "5") (pinfunction "NC._5") (pintype "passive+no_connect"))
    )
    (net (code "125") (name "unconnected-(U2-NC.-Pad8)") (class "Default")
      (node (ref "U2") (pin "8") (pinfunction "NC._8") (pintype "passive+no_connect"))
    )
    (net (code "126") (name "unconnected-(U2-NC.-Pad12)") (class "Default")
      (node (ref "U2") (pin "12") (pinfunction "NC._12") (pintype "passive+no_connect"))
    )
    (net (code "127") (name "unconnected-(U2-NC.-Pad13)") (class "Default")
      (node (ref "U2") (pin "13") (pinfunction "NC._13") (pintype "passive+no_connect"))
    )
    (net (code "128") (name "unconnected-(U2-NC.-Pad18)") (class "Default")
      (node (ref "U2") (pin "18") (pinfunction "NC._18") (pintype "passive+no_connect"))
    )
    (net (code "129") (name "unconnected-(U2-NC.-Pad23)") (class "Default")
      (node (ref "U2") (pin "23") (pinfunction "NC._23") (pintype "passive+no_connect"))
    )
    (net (code "130") (name "unconnected-(U2-NC.-Pad26)") (class "Default")
      (node (ref "U2") (pin "26") (pinfunction "NC._26") (pintype "passive+no_connect"))
    )
    (net (code "131") (name "unconnected-(U2-NC.-Pad30)") (class "Default")
      (node (ref "U2") (pin "30") (pinfunction "NC._30") (pintype "passive+no_connect"))
    )
    (net (code "132") (name "unconnected-(U2-NC.-Pad65)") (class "Default")
      (node (ref "U2") (pin "65") (pinfunction "NC._65") (pintype "passive+no_connect"))
    )
    (net (code "133") (name "unconnected-(U2-NC.-Pad66)") (class "Default")
      (node (ref "U2") (pin "66") (pinfunction "NC._66") (pintype "passive+no_connect"))
    )
    (net (code "134") (name "unconnected-(U2-NC.-Pad72)") (class "Default")
      (node (ref "U2") (pin "72") (pinfunction "NC._72") (pintype "passive+no_connect"))
    )
    (net (code "135") (name "unconnected-(U2-NC.-Pad73)") (class "Default")
      (node (ref "U2") (pin "73") (pinfunction "NC._73") (pintype "passive+no_connect"))
    )
    (net (code "136") (name "unconnected-(U2-NC.-Pad92)") (class "Default")
      (node (ref "U2") (pin "92") (pinfunction "NC._92") (pintype "passive+no_connect"))
    )
    (net (code "137") (name "unconnected-(U2-NC.-Pad108)") (class "Default")
      (node (ref "U2") (pin "108") (pinfunction "NC._108") (pintype "passive+no_connect"))
    )
    (net (code "138") (name "unconnected-(U2-NC.-Pad127)") (class "Default")
      (node (ref "U2") (pin "127") (pinfunction "NC._127") (pintype "passive+no_connect"))
    )
    (net (code "139") (name "unconnected-(U2-NC.-Pad128)") (class "Default")
      (node (ref "U2") (pin "128") (pinfunction "NC._128") (pintype "passive+no_connect"))
    )
  )
)
